# test_jig.net
KiCad netlist of a schematic drawn in EAGLE
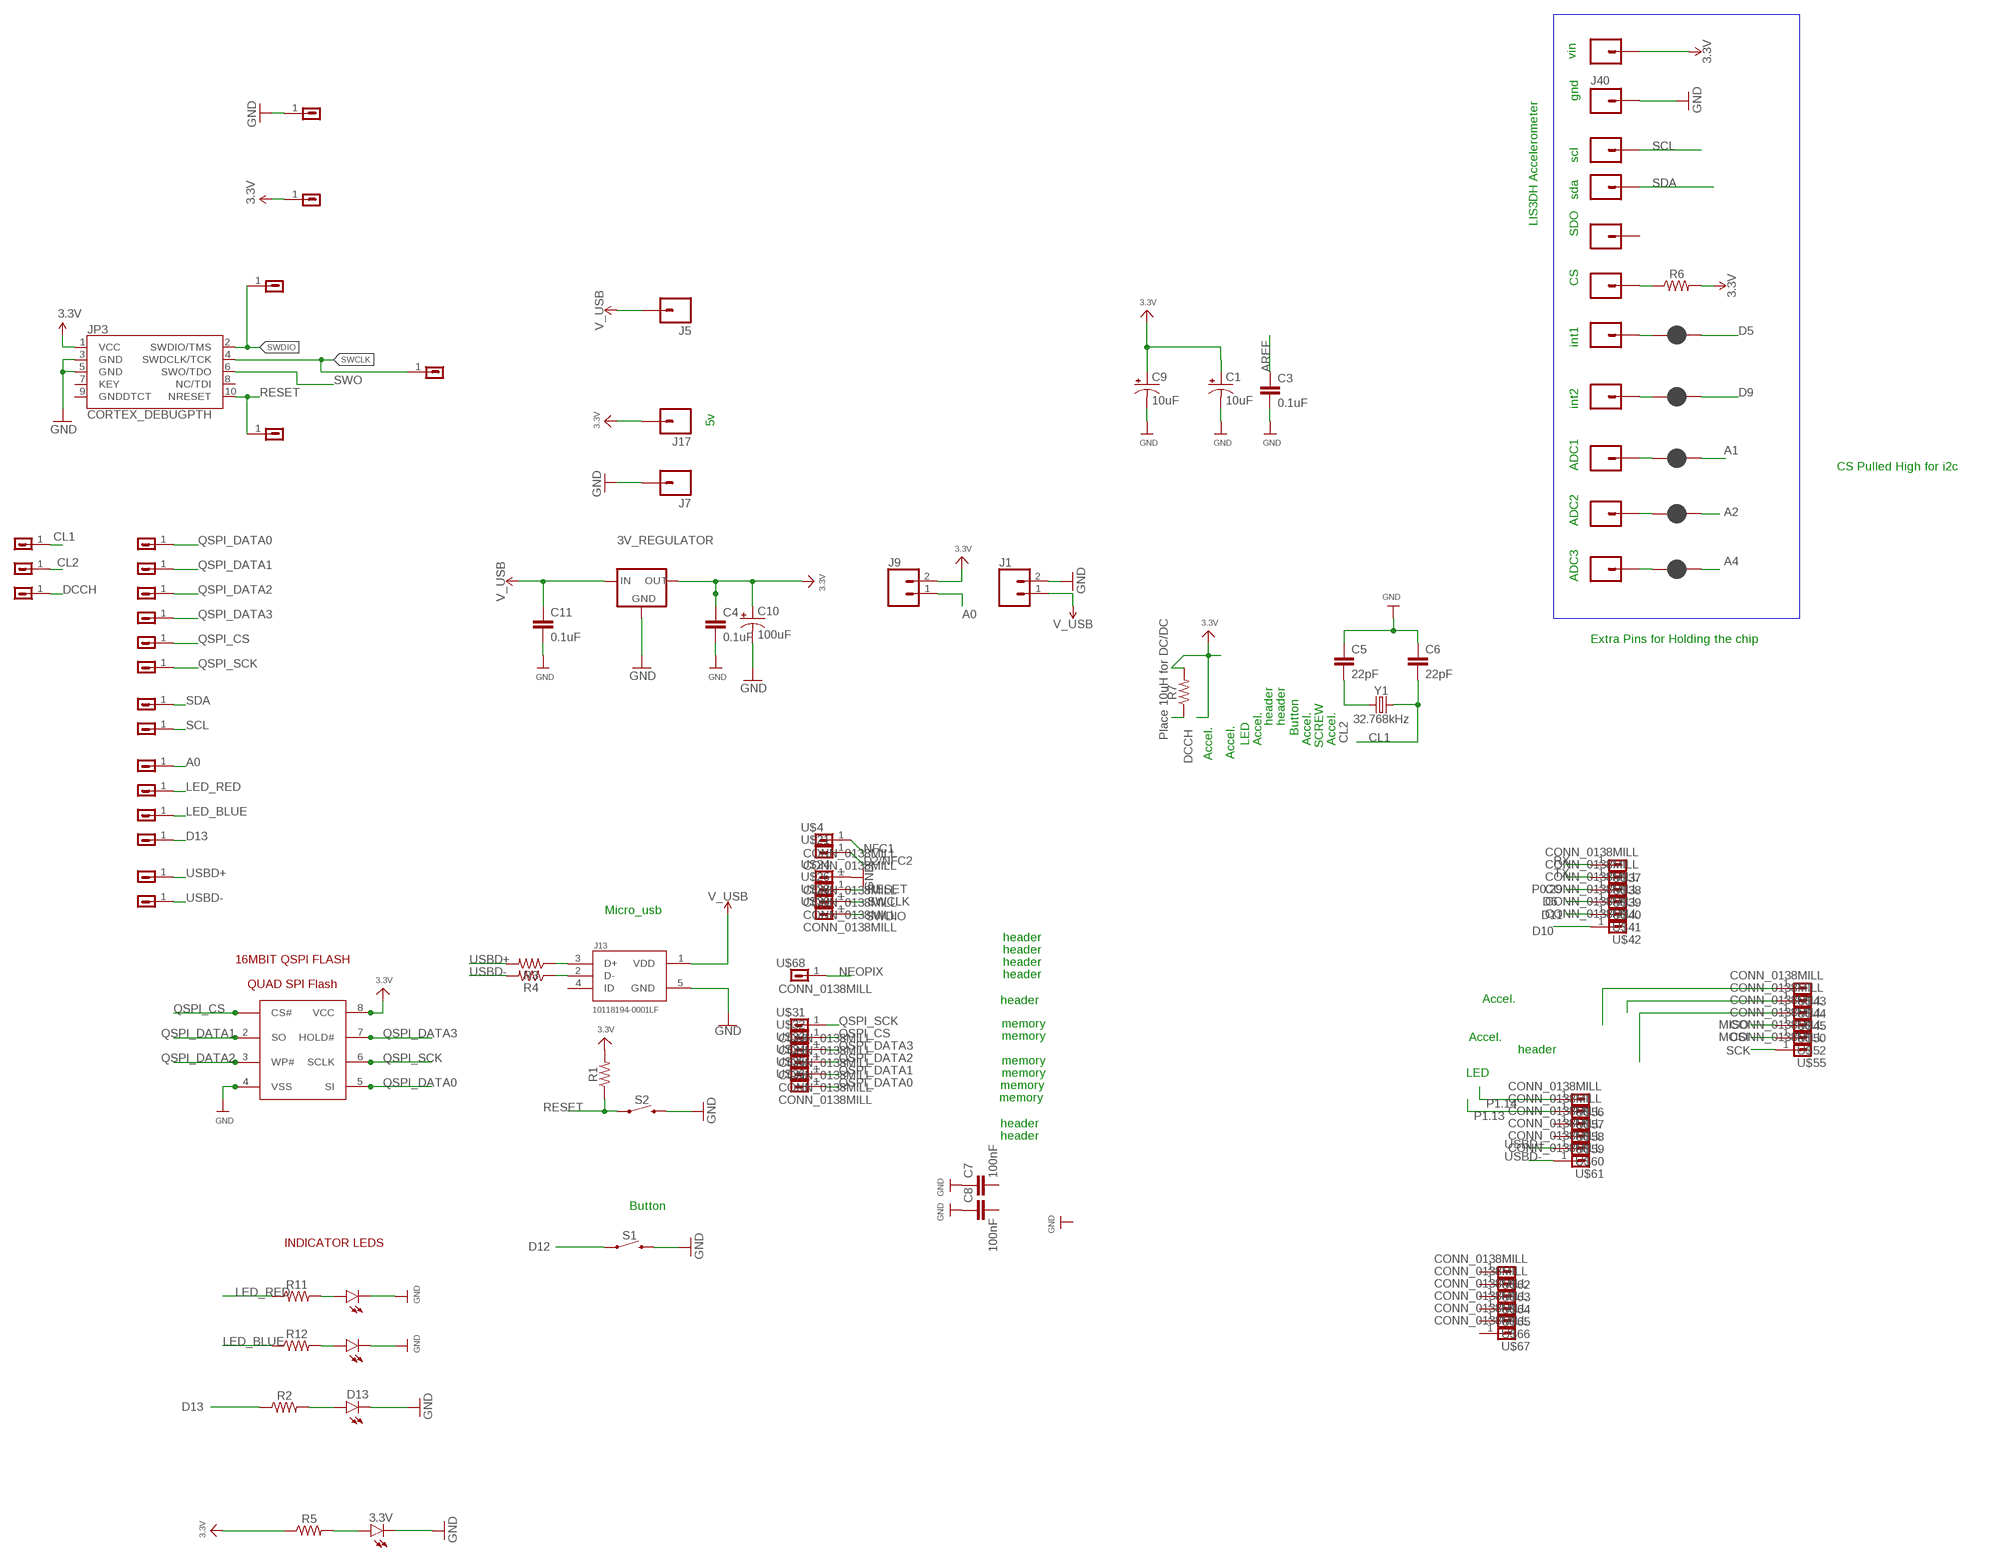
[diagram p0: schematic, sheet 1]

(export (version "E")
  (design (tool "Eeschema 10.0.6"))
  (components
    (comp (ref "3.3V")
      (value "LED5MM-KIT")
      (footprint "eagle-import:LED5MM-KIT")
      (libsource (lib "eagle-import") (part "LED5MM-KIT"))
    )
    (comp (ref "3V_REGULATOR")
      (value "LDL1117_5V_REG")
      (footprint "eagle-import:SOT223")
      (libsource (lib "eagle-import") (part "LDL1117_5V_REG"))
    )
    (comp (ref "C1")
      (value "10uF")
      (footprint "eagle-import:CPOL-RADIAL-2.5MM-5MM-KIT")
      (libsource (lib "eagle-import") (part "10UF-POLAR-RADIAL-2.5MM-KIT-25V-20%"))
    )
    (comp (ref "C3")
      (value "0.1uF")
      (footprint "eagle-import:CAP-PTH-SMALL-KIT")
      (libsource (lib "eagle-import") (part "0.1UF-KIT-EZ-50V-20%"))
    )
    (comp (ref "C4")
      (value "0.1uF")
      (footprint "eagle-import:CAP-PTH-SMALL-KIT")
      (libsource (lib "eagle-import") (part "0.1UF-KIT-EZ-50V-20%"))
    )
    (comp (ref "C5")
      (value "22pF")
      (footprint "eagle-import:CAP-PTH-SMALL-KIT")
      (libsource (lib "eagle-import") (part "0.1UF-KIT-EZ-50V-20%"))
    )
    (comp (ref "C6")
      (value "22pF")
      (footprint "eagle-import:CAP-PTH-SMALL-KIT")
      (libsource (lib "eagle-import") (part "0.1UF-KIT-EZ-50V-20%"))
    )
    (comp (ref "C7")
      (value "100nF")
      (footprint "eagle-import:0805")
      (libsource (lib "eagle-import") (part "10UF-0805-10V-10%"))
    )
    (comp (ref "C8")
      (value "100nF")
      (footprint "eagle-import:0805")
      (libsource (lib "eagle-import") (part "10UF-0805-10V-10%"))
    )
    (comp (ref "C9")
      (value "10uF")
      (footprint "eagle-import:CPOL-RADIAL-2.5MM-5MM-KIT")
      (libsource (lib "eagle-import") (part "10UF-POLAR-RADIAL-2.5MM-KIT-25V-20%"))
    )
    (comp (ref "C10")
      (value "100uF")
      (footprint "eagle-import:CPOL-RADIAL-2.5MM-6.5MM")
      (libsource (lib "eagle-import") (part "100UF-POLAR-RADIAL-2.5MM-25V-20%"))
    )
    (comp (ref "C11")
      (value "0.1uF")
      (footprint "eagle-import:CAP-PTH-SMALL-KIT")
      (libsource (lib "eagle-import") (part "0.1UF-KIT-EZ-50V-20%"))
    )
    (comp (ref "D2")
      (value "LED5MM-KIT")
      (footprint "eagle-import:LED5MM-KIT")
      (libsource (lib "eagle-import") (part "LED5MM-KIT"))
    )
    (comp (ref "D3")
      (value "LED5MM-KIT")
      (footprint "eagle-import:LED5MM-KIT")
      (libsource (lib "eagle-import") (part "LED5MM-KIT"))
    )
    (comp (ref "D13")
      (value "LED5MM-KIT")
      (footprint "eagle-import:LED5MM-KIT")
      (libsource (lib "eagle-import") (part "LED5MM-KIT"))
    )
    (comp (ref "J1")
      (value "CONN_025MM")
      (footprint "eagle-import:SCREWTERMINAL-5MM-2")
      (libsource (lib "eagle-import") (part "CONN_025MM"))
    )
    (comp (ref "J5")
      (value "M01PTH")
      (footprint "eagle-import:1X01")
      (libsource (lib "eagle-import") (part "M01PTH"))
    )
    (comp (ref "J7")
      (value "M01PTH")
      (footprint "eagle-import:1X01")
      (libsource (lib "eagle-import") (part "M01PTH"))
    )
    (comp (ref "J9")
      (value "CONN_025MM")
      (footprint "eagle-import:SCREWTERMINAL-5MM-2")
      (libsource (lib "eagle-import") (part "CONN_025MM"))
    )
    (comp (ref "J13")
      (value "10118194-0001LF")
      (footprint "eagle-import:FRAMATOME_10118194-0001LF")
      (fields (field (name "MF") "Amphenol ICC"))
      (libsource (lib "eagle-import") (part "10118194-0001LF"))
    )
    (comp (ref "J17")
      (value "M01PTH")
      (footprint "eagle-import:1X01")
      (libsource (lib "eagle-import") (part "M01PTH"))
    )
    (comp (ref "J22")
      (value "M01PTH")
      (footprint "eagle-import:1X01")
      (libsource (lib "eagle-import") (part "M01PTH"))
    )
    (comp (ref "J23")
      (value "M01PTH")
      (footprint "eagle-import:1X01")
      (libsource (lib "eagle-import") (part "M01PTH"))
    )
    (comp (ref "J24")
      (value "M01PTH")
      (footprint "eagle-import:1X01")
      (libsource (lib "eagle-import") (part "M01PTH"))
    )
    (comp (ref "J25")
      (value "M01PTH")
      (footprint "eagle-import:1X01")
      (libsource (lib "eagle-import") (part "M01PTH"))
    )
    (comp (ref "J26")
      (value "M01PTH")
      (footprint "eagle-import:1X01")
      (libsource (lib "eagle-import") (part "M01PTH"))
    )
    (comp (ref "J27")
      (value "M01PTH")
      (footprint "eagle-import:1X01")
      (libsource (lib "eagle-import") (part "M01PTH"))
    )
    (comp (ref "J39")
      (value "M01PTH")
      (footprint "eagle-import:1X01")
      (libsource (lib "eagle-import") (part "M01PTH"))
    )
    (comp (ref "J40")
      (value "M01PTH")
      (footprint "eagle-import:1X01")
      (libsource (lib "eagle-import") (part "M01PTH"))
    )
    (comp (ref "J42")
      (value "M01PTH")
      (footprint "eagle-import:1X01")
      (libsource (lib "eagle-import") (part "M01PTH"))
    )
    (comp (ref "J43")
      (value "M01PTH")
      (footprint "eagle-import:1X01")
      (libsource (lib "eagle-import") (part "M01PTH"))
    )
    (comp (ref "J44")
      (value "M01PTH")
      (footprint "eagle-import:1X01")
      (libsource (lib "eagle-import") (part "M01PTH"))
    )
    (comp (ref "JP1")
      (value "JUMPER-SMT_2_NC_PASTE_SILK")
      (footprint "eagle-import:SMT-JUMPER_2_NC_PASTE_SILK")
      (libsource (lib "eagle-import") (part "JUMPER-SMT_2_NC_PASTE_SILK"))
    )
    (comp (ref "JP2")
      (value "JUMPER-SMT_2_NC_PASTE_SILK")
      (footprint "eagle-import:SMT-JUMPER_2_NC_PASTE_SILK")
      (libsource (lib "eagle-import") (part "JUMPER-SMT_2_NC_PASTE_SILK"))
    )
    (comp (ref "JP3")
      (value "CORTEX_DEBUGPTH")
      (footprint "eagle-import:2X5-PTH-1.27MM")
      (libsource (lib "eagle-import") (part "CORTEX_DEBUGPTH"))
    )
    (comp (ref "JP4")
      (value "JUMPER-SMT_2_NC_PASTE_SILK")
      (footprint "eagle-import:SMT-JUMPER_2_NC_PASTE_SILK")
      (libsource (lib "eagle-import") (part "JUMPER-SMT_2_NC_PASTE_SILK"))
    )
    (comp (ref "JP6")
      (value "JUMPER-SMT_2_NC_PASTE_SILK")
      (footprint "eagle-import:SMT-JUMPER_2_NC_PASTE_SILK")
      (libsource (lib "eagle-import") (part "JUMPER-SMT_2_NC_PASTE_SILK"))
    )
    (comp (ref "JP7")
      (value "JUMPER-SMT_2_NC_PASTE_SILK")
      (footprint "eagle-import:SMT-JUMPER_2_NC_PASTE_SILK")
      (libsource (lib "eagle-import") (part "JUMPER-SMT_2_NC_PASTE_SILK"))
    )
    (comp (ref "R1")
      (value "RESISTORAXIAL-0.3")
      (footprint "eagle-import:AXIAL-0.3")
      (libsource (lib "eagle-import") (part "RESISTORAXIAL-0.3"))
    )
    (comp (ref "R2")
      (value "RESISTORAXIAL-0.3")
      (footprint "eagle-import:AXIAL-0.3")
      (libsource (lib "eagle-import") (part "RESISTORAXIAL-0.3"))
    )
    (comp (ref "R3")
      (value "RESISTORAXIAL-0.3")
      (footprint "eagle-import:AXIAL-0.3")
      (libsource (lib "eagle-import") (part "RESISTORAXIAL-0.3"))
    )
    (comp (ref "R4")
      (value "RESISTORAXIAL-0.3")
      (footprint "eagle-import:AXIAL-0.3")
      (libsource (lib "eagle-import") (part "RESISTORAXIAL-0.3"))
    )
    (comp (ref "R5")
      (value "RESISTORAXIAL-0.3")
      (footprint "eagle-import:AXIAL-0.3")
      (libsource (lib "eagle-import") (part "RESISTORAXIAL-0.3"))
    )
    (comp (ref "R6")
      (value "RESISTORAXIAL-0.3")
      (footprint "eagle-import:AXIAL-0.3")
      (libsource (lib "eagle-import") (part "RESISTORAXIAL-0.3"))
    )
    (comp (ref "R7")
      (value "RESISTORAXIAL-0.3")
      (footprint "eagle-import:AXIAL-0.3")
      (libsource (lib "eagle-import") (part "RESISTORAXIAL-0.3"))
    )
    (comp (ref "R11")
      (value "RESISTORAXIAL-0.3")
      (footprint "eagle-import:AXIAL-0.3")
      (libsource (lib "eagle-import") (part "RESISTORAXIAL-0.3"))
    )
    (comp (ref "R12")
      (value "RESISTORAXIAL-0.3")
      (footprint "eagle-import:AXIAL-0.3")
      (libsource (lib "eagle-import") (part "RESISTORAXIAL-0.3"))
    )
    (comp (ref "S1")
      (value "MOMENTARY-SWITCH-SPST-PTH-12MM")
      (footprint "eagle-import:TACTILE_SWITCH_PTH_12MM")
      (libsource (lib "eagle-import") (part "MOMENTARY-SWITCH-SPST-PTH-12MM"))
    )
    (comp (ref "S2")
      (value "MOMENTARY-SWITCH-SPST-PTH-12MM")
      (footprint "eagle-import:TACTILE_SWITCH_PTH_12MM")
      (libsource (lib "eagle-import") (part "MOMENTARY-SWITCH-SPST-PTH-12MM"))
    )
    (comp (ref "U$4")
      (value "CONN_0138MILL")
      (footprint "eagle-import:1X01-40MILL")
      (libsource (lib "eagle-import") (part "CONN_0138MILL"))
    )
    (comp (ref "U$13")
      (value "CONN_0143MILL")
      (footprint "eagle-import:1X01-43MILL")
      (libsource (lib "eagle-import") (part "CONN_0143MILL"))
    )
    (comp (ref "U$18")
      (value "CONN_0143MILL")
      (footprint "eagle-import:1X01-43MILL")
      (libsource (lib "eagle-import") (part "CONN_0143MILL"))
    )
    (comp (ref "U$19")
      (value "CONN_0143MILL")
      (footprint "eagle-import:1X01-43MILL")
      (libsource (lib "eagle-import") (part "CONN_0143MILL"))
    )
    (comp (ref "U$20")
      (value "CONN_0143MILL")
      (footprint "eagle-import:1X01-43MILL")
      (libsource (lib "eagle-import") (part "CONN_0143MILL"))
    )
    (comp (ref "U$21")
      (value "CONN_0138MILL")
      (footprint "eagle-import:1X01-40MILL")
      (libsource (lib "eagle-import") (part "CONN_0138MILL"))
    )
    (comp (ref "U$22")
      (value "CONN_0143MILL")
      (footprint "eagle-import:1X01-43MILL")
      (libsource (lib "eagle-import") (part "CONN_0143MILL"))
    )
    (comp (ref "U$23")
      (value "CONN_0143MILL")
      (footprint "eagle-import:1X01-43MILL")
      (libsource (lib "eagle-import") (part "CONN_0143MILL"))
    )
    (comp (ref "U$24")
      (value "CONN_0138MILL")
      (footprint "eagle-import:1X01-40MILL")
      (libsource (lib "eagle-import") (part "CONN_0138MILL"))
    )
    (comp (ref "U$26")
      (value "CONN_0138MILL")
      (footprint "eagle-import:1X01-40MILL")
      (libsource (lib "eagle-import") (part "CONN_0138MILL"))
    )
    (comp (ref "U$28")
      (value "CONN_0138MILL")
      (footprint "eagle-import:1X01-40MILL")
      (libsource (lib "eagle-import") (part "CONN_0138MILL"))
    )
    (comp (ref "U$29")
      (value "QUAD_SPI_FLASHSOIC8_300MIL")
      (footprint "eagle-import:SOIC8")
      (libsource (lib "eagle-import") (part "QUAD_SPI_FLASHSOIC8_300MIL"))
    )
    (comp (ref "U$30")
      (value "CONN_0138MILL")
      (footprint "eagle-import:1X01-40MILL")
      (libsource (lib "eagle-import") (part "CONN_0138MILL"))
    )
    (comp (ref "U$31")
      (value "CONN_0138MILL")
      (footprint "eagle-import:1X01-40MILL")
      (libsource (lib "eagle-import") (part "CONN_0138MILL"))
    )
    (comp (ref "U$32")
      (value "CONN_0138MILL")
      (footprint "eagle-import:1X01-40MILL")
      (libsource (lib "eagle-import") (part "CONN_0138MILL"))
    )
    (comp (ref "U$33")
      (value "CONN_0138MILL")
      (footprint "eagle-import:1X01-40MILL")
      (libsource (lib "eagle-import") (part "CONN_0138MILL"))
    )
    (comp (ref "U$34")
      (value "CONN_0138MILL")
      (footprint "eagle-import:1X01-40MILL")
      (libsource (lib "eagle-import") (part "CONN_0138MILL"))
    )
    (comp (ref "U$35")
      (value "CONN_0138MILL")
      (footprint "eagle-import:1X01-40MILL")
      (libsource (lib "eagle-import") (part "CONN_0138MILL"))
    )
    (comp (ref "U$36")
      (value "CONN_0138MILL")
      (footprint "eagle-import:1X01-40MILL")
      (libsource (lib "eagle-import") (part "CONN_0138MILL"))
    )
    (comp (ref "U$37")
      (value "CONN_0138MILL")
      (footprint "eagle-import:1X01-40MILL")
      (libsource (lib "eagle-import") (part "CONN_0138MILL"))
    )
    (comp (ref "U$38")
      (value "CONN_0138MILL")
      (footprint "eagle-import:1X01-40MILL")
      (libsource (lib "eagle-import") (part "CONN_0138MILL"))
    )
    (comp (ref "U$39")
      (value "CONN_0138MILL")
      (footprint "eagle-import:1X01-40MILL")
      (libsource (lib "eagle-import") (part "CONN_0138MILL"))
    )
    (comp (ref "U$40")
      (value "CONN_0138MILL")
      (footprint "eagle-import:1X01-40MILL")
      (libsource (lib "eagle-import") (part "CONN_0138MILL"))
    )
    (comp (ref "U$41")
      (value "CONN_0138MILL")
      (footprint "eagle-import:1X01-40MILL")
      (libsource (lib "eagle-import") (part "CONN_0138MILL"))
    )
    (comp (ref "U$42")
      (value "CONN_0138MILL")
      (footprint "eagle-import:1X01-40MILL")
      (libsource (lib "eagle-import") (part "CONN_0138MILL"))
    )
    (comp (ref "U$43")
      (value "CONN_0138MILL")
      (footprint "eagle-import:1X01-40MILL")
      (libsource (lib "eagle-import") (part "CONN_0138MILL"))
    )
    (comp (ref "U$44")
      (value "CONN_0138MILL")
      (footprint "eagle-import:1X01-40MILL")
      (libsource (lib "eagle-import") (part "CONN_0138MILL"))
    )
    (comp (ref "U$45")
      (value "CONN_0138MILL")
      (footprint "eagle-import:1X01-40MILL")
      (libsource (lib "eagle-import") (part "CONN_0138MILL"))
    )
    (comp (ref "U$50")
      (value "CONN_0138MILL")
      (footprint "eagle-import:1X01-40MILL")
      (libsource (lib "eagle-import") (part "CONN_0138MILL"))
    )
    (comp (ref "U$52")
      (value "CONN_0138MILL")
      (footprint "eagle-import:1X01-40MILL")
      (libsource (lib "eagle-import") (part "CONN_0138MILL"))
    )
    (comp (ref "U$55")
      (value "CONN_0138MILL")
      (footprint "eagle-import:1X01-40MILL")
      (libsource (lib "eagle-import") (part "CONN_0138MILL"))
    )
    (comp (ref "U$56")
      (value "CONN_0138MILL")
      (footprint "eagle-import:1X01-40MILL")
      (libsource (lib "eagle-import") (part "CONN_0138MILL"))
    )
    (comp (ref "U$57")
      (value "CONN_0138MILL")
      (footprint "eagle-import:1X01-40MILL")
      (libsource (lib "eagle-import") (part "CONN_0138MILL"))
    )
    (comp (ref "U$58")
      (value "CONN_0138MILL")
      (footprint "eagle-import:1X01-40MILL")
      (libsource (lib "eagle-import") (part "CONN_0138MILL"))
    )
    (comp (ref "U$59")
      (value "CONN_0138MILL")
      (footprint "eagle-import:1X01-40MILL")
      (libsource (lib "eagle-import") (part "CONN_0138MILL"))
    )
    (comp (ref "U$60")
      (value "CONN_0138MILL")
      (footprint "eagle-import:1X01-40MILL")
      (libsource (lib "eagle-import") (part "CONN_0138MILL"))
    )
    (comp (ref "U$61")
      (value "CONN_0138MILL")
      (footprint "eagle-import:1X01-40MILL")
      (libsource (lib "eagle-import") (part "CONN_0138MILL"))
    )
    (comp (ref "U$62")
      (value "CONN_0138MILL")
      (footprint "eagle-import:1X01-40MILL")
      (libsource (lib "eagle-import") (part "CONN_0138MILL"))
    )
    (comp (ref "U$63")
      (value "CONN_0138MILL")
      (footprint "eagle-import:1X01-40MILL")
      (libsource (lib "eagle-import") (part "CONN_0138MILL"))
    )
    (comp (ref "U$64")
      (value "CONN_0138MILL")
      (footprint "eagle-import:1X01-40MILL")
      (libsource (lib "eagle-import") (part "CONN_0138MILL"))
    )
    (comp (ref "U$65")
      (value "CONN_0138MILL")
      (footprint "eagle-import:1X01-40MILL")
      (libsource (lib "eagle-import") (part "CONN_0138MILL"))
    )
    (comp (ref "U$66")
      (value "CONN_0138MILL")
      (footprint "eagle-import:1X01-40MILL")
      (libsource (lib "eagle-import") (part "CONN_0138MILL"))
    )
    (comp (ref "U$67")
      (value "CONN_0138MILL")
      (footprint "eagle-import:1X01-40MILL")
      (libsource (lib "eagle-import") (part "CONN_0138MILL"))
    )
    (comp (ref "U$68")
      (value "CONN_0138MILL")
      (footprint "eagle-import:1X01-40MILL")
      (libsource (lib "eagle-import") (part "CONN_0138MILL"))
    )
    (comp (ref "U$69")
      (value "CONN_0143MILL")
      (footprint "eagle-import:1X01-43MILL")
      (libsource (lib "eagle-import") (part "CONN_0143MILL"))
    )
    (comp (ref "U$70")
      (value "CONN_0143MILL")
      (footprint "eagle-import:1X01-43MILL")
      (libsource (lib "eagle-import") (part "CONN_0143MILL"))
    )
    (comp (ref "U$71")
      (value "CONN_0143MILL")
      (footprint "eagle-import:1X01-43MILL")
      (libsource (lib "eagle-import") (part "CONN_0143MILL"))
    )
    (comp (ref "U$72")
      (value "CONN_0143MILL")
      (footprint "eagle-import:1X01-43MILL")
      (libsource (lib "eagle-import") (part "CONN_0143MILL"))
    )
    (comp (ref "U$73")
      (value "CONN_0143MILL")
      (footprint "eagle-import:1X01-43MILL")
      (libsource (lib "eagle-import") (part "CONN_0143MILL"))
    )
    (comp (ref "U$74")
      (value "CONN_0143MILL")
      (footprint "eagle-import:1X01-43MILL")
      (libsource (lib "eagle-import") (part "CONN_0143MILL"))
    )
    (comp (ref "U$75")
      (value "CONN_0143MILL")
      (footprint "eagle-import:1X01-43MILL")
      (libsource (lib "eagle-import") (part "CONN_0143MILL"))
    )
    (comp (ref "U$76")
      (value "CONN_0143MILL")
      (footprint "eagle-import:1X01-43MILL")
      (libsource (lib "eagle-import") (part "CONN_0143MILL"))
    )
    (comp (ref "U$77")
      (value "CONN_0143MILL")
      (footprint "eagle-import:1X01-43MILL")
      (libsource (lib "eagle-import") (part "CONN_0143MILL"))
    )
    (comp (ref "U$78")
      (value "CONN_0143MILL")
      (footprint "eagle-import:1X01-43MILL")
      (libsource (lib "eagle-import") (part "CONN_0143MILL"))
    )
    (comp (ref "U$79")
      (value "CONN_0143MILL")
      (footprint "eagle-import:1X01-43MILL")
      (libsource (lib "eagle-import") (part "CONN_0143MILL"))
    )
    (comp (ref "U$80")
      (value "CONN_0143MILL")
      (footprint "eagle-import:1X01-43MILL")
      (libsource (lib "eagle-import") (part "CONN_0143MILL"))
    )
    (comp (ref "U$81")
      (value "CONN_0143MILL")
      (footprint "eagle-import:1X01-43MILL")
      (libsource (lib "eagle-import") (part "CONN_0143MILL"))
    )
    (comp (ref "U$82")
      (value "CONN_0143MILL")
      (footprint "eagle-import:1X01-43MILL")
      (libsource (lib "eagle-import") (part "CONN_0143MILL"))
    )
    (comp (ref "U$83")
      (value "CONN_0143MILL")
      (footprint "eagle-import:1X01-43MILL")
      (libsource (lib "eagle-import") (part "CONN_0143MILL"))
    )
    (comp (ref "U$84")
      (value "CONN_0143MILL")
      (footprint "eagle-import:1X01-43MILL")
      (libsource (lib "eagle-import") (part "CONN_0143MILL"))
    )
    (comp (ref "Y1")
      (value "32.768kHz")
      (footprint "eagle-import:CRYSTAL-PTH-2X6-CYL")
      (libsource (lib "eagle-import") (part "CRYSTAL-32.768KHZPTH-2X6"))
    )
  )
  (nets
    (net (code "1") (name "/A0") (class "Default")
      (node (ref "J9") (pin "1") (pinfunction "1_1") (pintype "passive"))
      (node (ref "U$76") (pin "1") (pinfunction "1_1") (pintype "passive"))
    )
    (net (code "2") (name "/A1") (class "Default")
      (node (ref "JP4") (pin "2") (pinfunction "2_2") (pintype "passive"))
    )
    (net (code "3") (name "/A2") (class "Default")
      (node (ref "JP6") (pin "2") (pinfunction "2_2") (pintype "passive"))
    )
    (net (code "4") (name "/A4") (class "Default")
      (node (ref "JP7") (pin "2") (pinfunction "2_2") (pintype "passive"))
    )
    (net (code "5") (name "/AREF") (class "Default")
      (node (ref "C3") (pin "1") (pinfunction "1_1") (pintype "passive"))
      (node (ref "U$43") (pin "1") (pinfunction "1_1") (pintype "passive"))
    )
    (net (code "6") (name "/CL1") (class "Default")
      (node (ref "C6") (pin "2") (pinfunction "2_2") (pintype "passive"))
      (node (ref "U$82") (pin "1") (pinfunction "1_1") (pintype "passive"))
      (node (ref "Y1") (pin "2") (pinfunction "2_2") (pintype "passive"))
    )
    (net (code "7") (name "/CL2") (class "Default")
      (node (ref "C5") (pin "2") (pinfunction "2_2") (pintype "passive"))
      (node (ref "U$83") (pin "1") (pinfunction "1_1") (pintype "passive"))
      (node (ref "Y1") (pin "1") (pinfunction "1_1") (pintype "passive"))
    )
    (net (code "8") (name "/D2{slash}NFC2") (class "Default")
      (node (ref "U$21") (pin "1") (pinfunction "1_1") (pintype "passive"))
    )
    (net (code "9") (name "/D5") (class "Default")
      (node (ref "JP1") (pin "2") (pinfunction "2_2") (pintype "passive"))
    )
    (net (code "10") (name "/D6") (class "Default")
      (node (ref "U$40") (pin "1") (pinfunction "1_1") (pintype "passive"))
    )
    (net (code "11") (name "/D9") (class "Default")
      (node (ref "JP2") (pin "2") (pinfunction "2_2") (pintype "passive"))
    )
    (net (code "12") (name "/D10") (class "Default")
      (node (ref "U$42") (pin "1") (pinfunction "1_1") (pintype "passive"))
    )
    (net (code "13") (name "/D11") (class "Default")
      (node (ref "U$41") (pin "1") (pinfunction "1_1") (pintype "passive"))
    )
    (net (code "14") (name "/D12") (class "Default")
      (node (ref "S1") (pin "1") (pinfunction "1_1") (pintype "passive"))
    )
    (net (code "15") (name "/D13") (class "Default")
      (node (ref "R2") (pin "P$1") (pinfunction "1_P$1") (pintype "passive"))
      (node (ref "U$79") (pin "1") (pinfunction "1_1") (pintype "passive"))
    )
    (net (code "16") (name "/DCCH") (class "Default")
      (node (ref "R7") (pin "P$1") (pinfunction "1_P$1") (pintype "passive"))
      (node (ref "U$84") (pin "1") (pinfunction "1_1") (pintype "passive"))
    )
    (net (code "17") (name "/LED_BLUE") (class "Default")
      (node (ref "R12") (pin "P$1") (pinfunction "1_P$1") (pintype "passive"))
      (node (ref "U$78") (pin "1") (pinfunction "1_1") (pintype "passive"))
    )
    (net (code "18") (name "/LED_RED") (class "Default")
      (node (ref "R11") (pin "P$1") (pinfunction "1_P$1") (pintype "passive"))
      (node (ref "U$77") (pin "1") (pinfunction "1_1") (pintype "passive"))
    )
    (net (code "19") (name "/MISO") (class "Default")
      (node (ref "U$50") (pin "1") (pinfunction "1_1") (pintype "passive"))
    )
    (net (code "20") (name "/MOSI") (class "Default")
      (node (ref "U$52") (pin "1") (pinfunction "1_1") (pintype "passive"))
    )
    (net (code "21") (name "/NEOPIX") (class "Default")
      (node (ref "U$68") (pin "1") (pinfunction "1_1") (pintype "passive"))
    )
    (net (code "22") (name "/NFC1") (class "Default")
      (node (ref "U$4") (pin "1") (pinfunction "1_1") (pintype "passive"))
    )
    (net (code "23") (name "/P0.29") (class "Default")
      (node (ref "U$39") (pin "1") (pinfunction "1_1") (pintype "passive"))
    )
    (net (code "24") (name "/P1.13") (class "Default")
      (node (ref "U$57") (pin "1") (pinfunction "1_1") (pintype "passive"))
    )
    (net (code "25") (name "/P1.14") (class "Default")
      (node (ref "U$56") (pin "1") (pinfunction "1_1") (pintype "passive"))
    )
    (net (code "26") (name "/QSPI_CS") (class "Default")
      (node (ref "U$29") (pin "1") (pinfunction "CS#_1") (pintype "bidirectional"))
      (node (ref "U$32") (pin "1") (pinfunction "1_1") (pintype "passive"))
      (node (ref "U$72") (pin "1") (pinfunction "1_1") (pintype "passive"))
    )
    (net (code "27") (name "/QSPI_DATA0") (class "Default")
      (node (ref "U$23") (pin "1") (pinfunction "1_1") (pintype "passive"))
      (node (ref "U$29") (pin "5") (pinfunction "SI_5") (pintype "bidirectional"))
      (node (ref "U$36") (pin "1") (pinfunction "1_1") (pintype "passive"))
    )
    (net (code "28") (name "/QSPI_DATA1") (class "Default")
      (node (ref "U$29") (pin "2") (pinfunction "SO_2") (pintype "bidirectional"))
      (node (ref "U$35") (pin "1") (pinfunction "1_1") (pintype "passive"))
      (node (ref "U$69") (pin "1") (pinfunction "1_1") (pintype "passive"))
    )
    (net (code "29") (name "/QSPI_DATA2") (class "Default")
      (node (ref "U$29") (pin "3") (pinfunction "WP#_3") (pintype "bidirectional"))
      (node (ref "U$34") (pin "1") (pinfunction "1_1") (pintype "passive"))
      (node (ref "U$70") (pin "1") (pinfunction "1_1") (pintype "passive"))
    )
    (net (code "30") (name "/QSPI_DATA3") (class "Default")
      (node (ref "U$29") (pin "7") (pinfunction "HOLD#_7") (pintype "bidirectional"))
      (node (ref "U$33") (pin "1") (pinfunction "1_1") (pintype "passive"))
      (node (ref "U$71") (pin "1") (pinfunction "1_1") (pintype "passive"))
    )
    (net (code "31") (name "/QSPI_SCK") (class "Default")
      (node (ref "U$29") (pin "6") (pinfunction "SCLK_6") (pintype "bidirectional"))
      (node (ref "U$31") (pin "1") (pinfunction "1_1") (pintype "passive"))
      (node (ref "U$73") (pin "1") (pinfunction "1_1") (pintype "passive"))
    )
    (net (code "32") (name "/RESET") (class "Default")
      (node (ref "JP3") (pin "10") (pinfunction "NRESET_10") (pintype "bidirectional"))
      (node (ref "R1") (pin "P$1") (pinfunction "1_P$1") (pintype "passive"))
      (node (ref "S2") (pin "1") (pinfunction "1_1") (pintype "passive"))
      (node (ref "U$20") (pin "1") (pinfunction "1_1") (pintype "passive"))
      (node (ref "U$26") (pin "1") (pinfunction "1_1") (pintype "passive"))
    )
    (net (code "33") (name "/RX") (class "Default")
      (node (ref "U$37") (pin "1") (pinfunction "1_1") (pintype "passive"))
    )
    (net (code "34") (name "/SCK") (class "Default")
      (node (ref "U$55") (pin "1") (pinfunction "1_1") (pintype "passive"))
    )
    (net (code "35") (name "/SCL") (class "Default")
      (node (ref "J43") (pin "1") (pinfunction "1_1") (pintype "passive"))
      (node (ref "U$75") (pin "1") (pinfunction "1_1") (pintype "passive"))
    )
    (net (code "36") (name "/SDA") (class "Default")
      (node (ref "J42") (pin "1") (pinfunction "1_1") (pintype "passive"))
      (node (ref "U$74") (pin "1") (pinfunction "1_1") (pintype "passive"))
    )
    (net (code "37") (name "/SWO") (class "Default")
      (node (ref "JP3") (pin "6") (pinfunction "SWO/TDO_6") (pintype "bidirectional"))
    )
    (net (code "38") (name "/TX") (class "Default")
      (node (ref "U$38") (pin "1") (pinfunction "1_1") (pintype "passive"))
    )
    (net (code "39") (name "/USBD+") (class "Default")
      (node (ref "R3") (pin "P$2") (pinfunction "2_P$2") (pintype "passive"))
      (node (ref "U$60") (pin "1") (pinfunction "1_1") (pintype "passive"))
      (node (ref "U$80") (pin "1") (pinfunction "1_1") (pintype "passive"))
    )
    (net (code "40") (name "/USBD-") (class "Default")
      (node (ref "R4") (pin "P$2") (pinfunction "2_P$2") (pintype "passive"))
      (node (ref "U$61") (pin "1") (pinfunction "1_1") (pintype "passive"))
      (node (ref "U$81") (pin "1") (pinfunction "1_1") (pintype "passive"))
    )
    (net (code "41") (name "3.3V") (class "Default")
      (node (ref "3V_REGULATOR") (pin "2") (pinfunction "OUT_2") (pintype "passive"))
      (node (ref "3V_REGULATOR") (pin "4") (pinfunction "OUT_4") (pintype "passive"))
      (node (ref "C1") (pin "1") (pinfunction "+_1") (pintype "passive"))
      (node (ref "C10") (pin "1") (pinfunction "+_1") (pintype "passive"))
      (node (ref "C4") (pin "1") (pinfunction "1_1") (pintype "passive"))
      (node (ref "C9") (pin "1") (pinfunction "+_1") (pintype "passive"))
      (node (ref "J17") (pin "1") (pinfunction "1_1") (pintype "passive"))
      (node (ref "J22") (pin "1") (pinfunction "1_1") (pintype "passive"))
      (node (ref "J9") (pin "2") (pinfunction "2_2") (pintype "passive"))
      (node (ref "JP3") (pin "1") (pinfunction "VCC_1") (pintype "bidirectional"))
      (node (ref "R1") (pin "P$2") (pinfunction "2_P$2") (pintype "passive"))
      (node (ref "R5") (pin "P$1") (pinfunction "1_P$1") (pintype "passive"))
      (node (ref "R6") (pin "P$2") (pinfunction "2_P$2") (pintype "passive"))
      (node (ref "R7") (pin "P$2") (pinfunction "2_P$2") (pintype "passive"))
      (node (ref "U$18") (pin "1") (pinfunction "1_1") (pintype "passive"))
      (node (ref "U$29") (pin "8") (pinfunction "VCC_8") (pintype "bidirectional"))
    )
    (net (code "42") (name "GND") (class "Default")
      (node (ref "3.3V") (pin "K") (pinfunction "C_K") (pintype "passive"))
      (node (ref "3V_REGULATOR") (pin "1") (pinfunction "GND_1") (pintype "input"))
      (node (ref "C1") (pin "2") (pinfunction "-_2") (pintype "passive"))
      (node (ref "C10") (pin "2") (pinfunction "-_2") (pintype "passive"))
      (node (ref "C11") (pin "2") (pinfunction "2_2") (pintype "passive"))
      (node (ref "C3") (pin "2") (pinfunction "2_2") (pintype "passive"))
      (node (ref "C4") (pin "2") (pinfunction "2_2") (pintype "passive"))
      (node (ref "C5") (pin "1") (pinfunction "1_1") (pintype "passive"))
      (node (ref "C6") (pin "1") (pinfunction "1_1") (pintype "passive"))
      (node (ref "C7") (pin "1") (pinfunction "1_1") (pintype "passive"))
      (node (ref "C8") (pin "1") (pinfunction "1_1") (pintype "passive"))
      (node (ref "C9") (pin "2") (pinfunction "-_2") (pintype "passive"))
      (node (ref "D13") (pin "K") (pinfunction "C_K") (pintype "passive"))
      (node (ref "D2") (pin "K") (pinfunction "C_K") (pintype "passive"))
      (node (ref "D3") (pin "K") (pinfunction "C_K") (pintype "passive"))
      (node (ref "J1") (pin "2") (pinfunction "2_2") (pintype "passive"))
      (node (ref "J13") (pin "5") (pinfunction "GND_5") (pintype "power_in"))
      (node (ref "J40") (pin "1") (pinfunction "1_1") (pintype "passive"))
      (node (ref "J7") (pin "1") (pinfunction "1_1") (pintype "passive"))
      (node (ref "JP3") (pin "3") (pinfunction "GND_3") (pintype "bidirectional"))
      (node (ref "JP3") (pin "5") (pinfunction "GND_5") (pintype "bidirectional"))
      (node (ref "S1") (pin "3") (pinfunction "2_3") (pintype "passive"))
      (node (ref "S2") (pin "3") (pinfunction "2_3") (pintype "passive"))
      (node (ref "U$13") (pin "1") (pinfunction "1_1") (pintype "passive"))
      (node (ref "U$24") (pin "1") (pinfunction "1_1") (pintype "passive"))
      (node (ref "U$29") (pin "4") (pinfunction "VSS_4") (pintype "bidirectional"))
    )
    (net (code "43") (name "Net-(J13-D+)") (class "Default")
      (node (ref "J13") (pin "3") (pinfunction "D+_3") (pintype "bidirectional"))
      (node (ref "R3") (pin "P$1") (pinfunction "1_P$1") (pintype "passive"))
    )
    (net (code "44") (name "Net-(J13-D-)") (class "Default")
      (node (ref "J13") (pin "2") (pinfunction "D-_2") (pintype "bidirectional"))
      (node (ref "R4") (pin "P$1") (pinfunction "1_P$1") (pintype "passive"))
    )
    (net (code "45") (name "Net-(J24-Pad1)") (class "Default")
      (node (ref "J24") (pin "1") (pinfunction "1_1") (pintype "passive"))
      (node (ref "JP6") (pin "1") (pinfunction "1_1") (pintype "passive"))
    )
    (net (code "46") (name "Net-(J25-Pad1)") (class "Default")
      (node (ref "J25") (pin "1") (pinfunction "1_1") (pintype "passive"))
      (node (ref "JP4") (pin "1") (pinfunction "1_1") (pintype "passive"))
    )
    (net (code "47") (name "Net-(J26-Pad1)") (class "Default")
      (node (ref "J26") (pin "1") (pinfunction "1_1") (pintype "passive"))
      (node (ref "JP2") (pin "1") (pinfunction "1_1") (pintype "passive"))
    )
    (net (code "48") (name "Net-(J27-Pad1)") (class "Default")
      (node (ref "J27") (pin "1") (pinfunction "1_1") (pintype "passive"))
      (node (ref "JP7") (pin "1") (pinfunction "1_1") (pintype "passive"))
    )
    (net (code "49") (name "Net-(J44-Pad1)") (class "Default")
      (node (ref "J44") (pin "1") (pinfunction "1_1") (pintype "passive"))
      (node (ref "JP1") (pin "1") (pinfunction "1_1") (pintype "passive"))
    )
    (net (code "50") (name "Net-(R2-2)") (class "Default")
      (node (ref "D13") (pin "A") (pinfunction "A_A") (pintype "passive"))
      (node (ref "R2") (pin "P$2") (pinfunction "2_P$2") (pintype "passive"))
    )
    (net (code "51") (name "Net-(R5-2)") (class "Default")
      (node (ref "3.3V") (pin "A") (pinfunction "A_A") (pintype "passive"))
      (node (ref "R5") (pin "P$2") (pinfunction "2_P$2") (pintype "passive"))
    )
    (net (code "52") (name "Net-(R6-1)") (class "Default")
      (node (ref "J23") (pin "1") (pinfunction "1_1") (pintype "passive"))
      (node (ref "R6") (pin "P$1") (pinfunction "1_P$1") (pintype "passive"))
    )
    (net (code "53") (name "Net-(R11-2)") (class "Default")
      (node (ref "D3") (pin "A") (pinfunction "A_A") (pintype "passive"))
      (node (ref "R11") (pin "P$2") (pinfunction "2_P$2") (pintype "passive"))
    )
    (net (code "54") (name "Net-(R12-2)") (class "Default")
      (node (ref "D2") (pin "A") (pinfunction "A_A") (pintype "passive"))
      (node (ref "R12") (pin "P$2") (pinfunction "2_P$2") (pintype "passive"))
    )
    (net (code "55") (name "SWCLK") (class "Default")
      (node (ref "JP3") (pin "4") (pinfunction "SWDCLK/TCK_4") (pintype "bidirectional"))
      (node (ref "U$22") (pin "1") (pinfunction "1_1") (pintype "passive"))
      (node (ref "U$28") (pin "1") (pinfunction "1_1") (pintype "passive"))
    )
    (net (code "56") (name "SWDIO") (class "Default")
      (node (ref "JP3") (pin "2") (pinfunction "SWDIO/TMS_2") (pintype "bidirectional"))
      (node (ref "U$19") (pin "1") (pinfunction "1_1") (pintype "passive"))
      (node (ref "U$30") (pin "1") (pinfunction "1_1") (pintype "passive"))
    )
    (net (code "57") (name "V_USB") (class "Default")
      (node (ref "3V_REGULATOR") (pin "3") (pinfunction "IN_3") (pintype "input"))
      (node (ref "C11") (pin "1") (pinfunction "1_1") (pintype "passive"))
      (node (ref "J1") (pin "1") (pinfunction "1_1") (pintype "passive"))
      (node (ref "J13") (pin "1") (pinfunction "VDD_1") (pintype "power_in"))
      (node (ref "J5") (pin "1") (pinfunction "1_1") (pintype "passive"))
    )
    (net (code "58") (name "unconnected-(C7-Pad2)") (class "Default")
      (node (ref "C7") (pin "2") (pinfunction "2_2") (pintype "passive"))
    )
    (net (code "59") (name "unconnected-(C8-Pad2)") (class "Default")
      (node (ref "C8") (pin "2") (pinfunction "2_2") (pintype "passive"))
    )
    (net (code "60") (name "unconnected-(J13-ID-Pad4)") (class "Default")
      (node (ref "J13") (pin "4") (pinfunction "ID_4") (pintype "passive"))
    )
    (net (code "61") (name "unconnected-(J39-Pad1)") (class "Default")
      (node (ref "J39") (pin "1") (pinfunction "1_1") (pintype "passive"))
    )
    (net (code "62") (name "unconnected-(JP3-GNDDTCT-Pad9)") (class "Default")
      (node (ref "JP3") (pin "9") (pinfunction "GNDDTCT_9") (pintype "bidirectional"))
    )
    (net (code "63") (name "unconnected-(JP3-KEY-Pad7)") (class "Default")
      (node (ref "JP3") (pin "7") (pinfunction "KEY_7") (pintype "bidirectional"))
    )
    (net (code "64") (name "unconnected-(JP3-NC{slash}TDI-Pad8)") (class "Default")
      (node (ref "JP3") (pin "8") (pinfunction "NC/TDI_8") (pintype "bidirectional"))
    )
    (net (code "65") (name "unconnected-(U$44-Pad1)") (class "Default")
      (node (ref "U$44") (pin "1") (pinfunction "1_1") (pintype "passive"))
    )
    (net (code "66") (name "unconnected-(U$45-Pad1)") (class "Default")
      (node (ref "U$45") (pin "1") (pinfunction "1_1") (pintype "passive"))
    )
    (net (code "67") (name "unconnected-(U$58-Pad1)") (class "Default")
      (node (ref "U$58") (pin "1") (pinfunction "1_1") (pintype "passive"))
    )
    (net (code "68") (name "unconnected-(U$59-Pad1)") (class "Default")
      (node (ref "U$59") (pin "1") (pinfunction "1_1") (pintype "passive"))
    )
    (net (code "69") (name "unconnected-(U$62-Pad1)") (class "Default")
      (node (ref "U$62") (pin "1") (pinfunction "1_1") (pintype "passive"))
    )
    (net (code "70") (name "unconnected-(U$63-Pad1)") (class "Default")
      (node (ref "U$63") (pin "1") (pinfunction "1_1") (pintype "passive"))
    )
    (net (code "71") (name "unconnected-(U$64-Pad1)") (class "Default")
      (node (ref "U$64") (pin "1") (pinfunction "1_1") (pintype "passive"))
    )
    (net (code "72") (name "unconnected-(U$65-Pad1)") (class "Default")
      (node (ref "U$65") (pin "1") (pinfunction "1_1") (pintype "passive"))
    )
    (net (code "73") (name "unconnected-(U$66-Pad1)") (class "Default")
      (node (ref "U$66") (pin "1") (pinfunction "1_1") (pintype "passive"))
    )
    (net (code "74") (name "unconnected-(U$67-Pad1)") (class "Default")
      (node (ref "U$67") (pin "1") (pinfunction "1_1") (pintype "passive"))
    )
  )
)
